# rftoy31.net
KiCad netlist of a schematic drawn in EAGLE
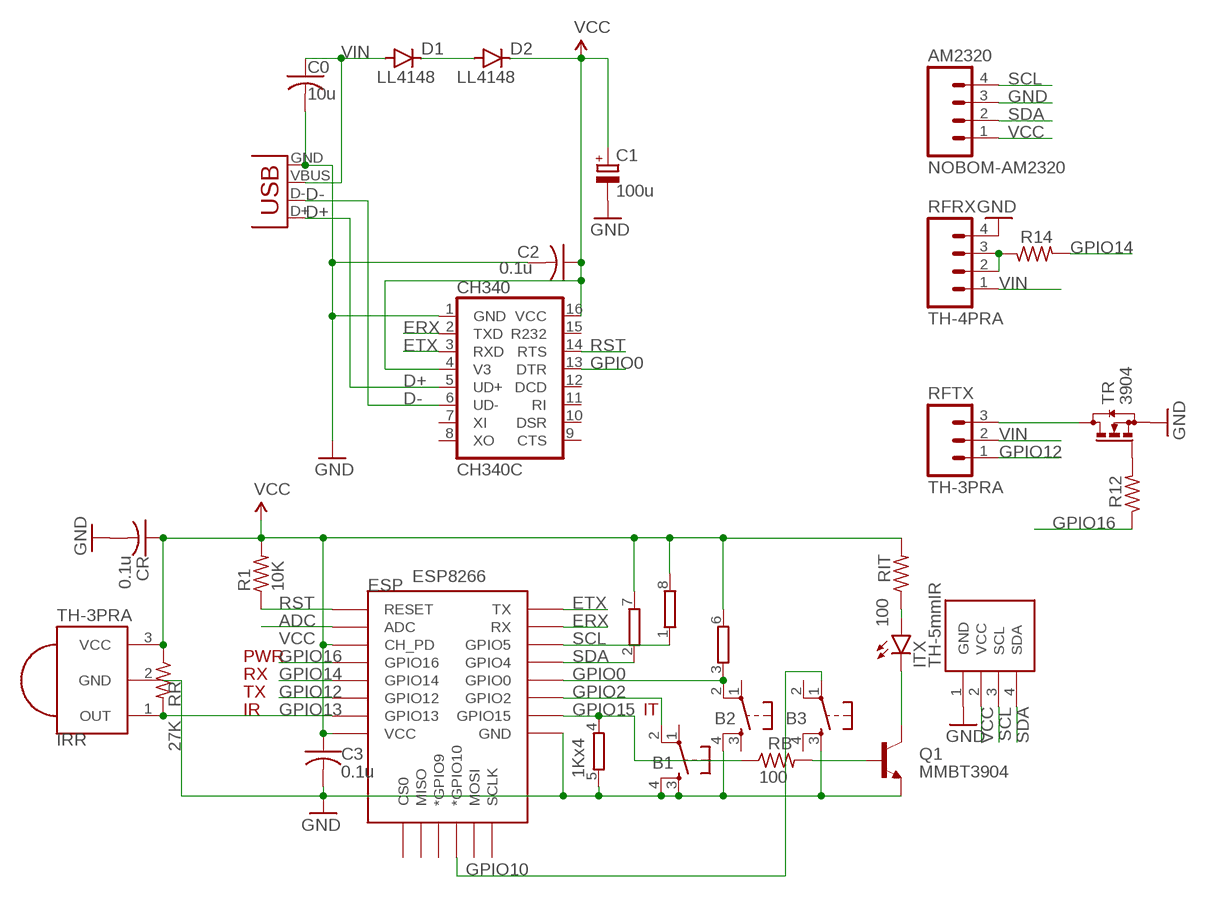
[diagram p0: schematic, sheet 1]

(export (version "E")
  (design (tool "Eeschema 10.0.6"))
  (components
    (comp (ref "AM2320")
      (value "NOBOM-AM2320")
      (footprint "eagle-import:1X04_NO_SILK")
      (libsource (lib "eagle-import") (part "M041X04_NO_SILK"))
    )
    (comp (ref "B1")
      (value "TH-TACT6x9")
      (footprint "eagle-import:EVQ-Q2-SMD")
      (libsource (lib "eagle-import") (part "SPST_TACT"))
    )
    (comp (ref "B2")
      (value "TH-TACT6x9")
      (footprint "eagle-import:EVQ-Q2-SMD")
      (libsource (lib "eagle-import") (part "SPST_TACT"))
    )
    (comp (ref "B3")
      (value "TH-TACT6x9")
      (footprint "eagle-import:EVQ-Q2-SMD")
      (libsource (lib "eagle-import") (part "SPST_TACT"))
    )
    (comp (ref "C0")
      (value "10u")
      (footprint "eagle-import:C0805K")
      (libsource (lib "eagle-import") (part "adafruit2013_C-USC0805K"))
    )
    (comp (ref "C1")
      (value "100u")
      (footprint "eagle-import:PANASONIC_C")
      (libsource (lib "eagle-import") (part "CPOL-EUC"))
    )
    (comp (ref "C2")
      (value "0.1u")
      (footprint "eagle-import:C0603K")
      (libsource (lib "eagle-import") (part "C-USC0603K"))
    )
    (comp (ref "C3")
      (value "0.1u")
      (footprint "eagle-import:C0603")
      (libsource (lib "eagle-import") (part "C-USC0603"))
    )
    (comp (ref "CH340")
      (value "CH340C")
      (footprint "eagle-import:SO16")
      (libsource (lib "eagle-import") (part "CH340G"))
    )
    (comp (ref "CR")
      (value "0.1u")
      (footprint "eagle-import:C0603")
      (libsource (lib "eagle-import") (part "C-USC0603"))
    )
    (comp (ref "D1")
      (value "LL4148")
      (footprint "eagle-import:MINIMELF")
      (libsource (lib "eagle-import") (part "DIODE-MINIMELF"))
    )
    (comp (ref "D2")
      (value "LL4148")
      (footprint "eagle-import:MINIMELF")
      (libsource (lib "eagle-import") (part "DIODE-MINIMELF"))
    )
    (comp (ref "ESP")
      (value "ESP8266")
      (footprint "eagle-import:ESP12E-SMD")
      (libsource (lib "eagle-import") (part "ESP12ESMD"))
    )
    (comp (ref "IRR")
      (value "TH-3PRA")
      (footprint "eagle-import:PNA460XM")
      (libsource (lib "eagle-import") (part "PNA460XM"))
    )
    (comp (ref "ITX")
      (value "TH-5mmIR")
      (footprint "eagle-import:IRL80A")
      (libsource (lib "eagle-import") (part "LEDIRL80A"))
    )
    (comp (ref "LCD")
      (value "NOBOM-OLED")
      (footprint "eagle-import:SSD1306_OLED_I2C_PCB_0.75_B")
      (libsource (lib "eagle-import") (part "SSD1306_OLED_I2CPCB0.75B"))
    )
    (comp (ref "Q1")
      (value "MMBT3904")
      (footprint "eagle-import:SOT23")
      (libsource (lib "eagle-import") (part "TRANSISTOR_NPNSOT23"))
    )
    (comp (ref "R1")
      (value "10K")
      (footprint "eagle-import:R0603")
      (libsource (lib "eagle-import") (part "R-US_R0603"))
    )
    (comp (ref "R12")
      (value "1K")
      (footprint "eagle-import:R0603")
      (libsource (lib "eagle-import") (part "adafruitGood_R-US_R0603"))
    )
    (comp (ref "R14")
      (value "1K")
      (footprint "eagle-import:R0603")
      (libsource (lib "eagle-import") (part "adafruitGood_R-US_R0603"))
    )
    (comp (ref "RB")
      (value "100")
      (footprint "eagle-import:R0603")
      (libsource (lib "eagle-import") (part "R-US_R0603"))
    )
    (comp (ref "RFRX")
      (value "TH-4PRA")
      (footprint "eagle-import:1X04_LONGPADS")
      (libsource (lib "eagle-import") (part "M04LONGPADS"))
    )
    (comp (ref "RFTX")
      (value "TH-3PRA")
      (footprint "eagle-import:1X03_NO_SILK")
      (libsource (lib "eagle-import") (part "M031X03_NO_SILK"))
    )
    (comp (ref "RIT")
      (value "100")
      (footprint "eagle-import:R0603")
      (libsource (lib "eagle-import") (part "R-US_R0603"))
    )
    (comp (ref "RN1")
      (value "1Kx4")
      (footprint "eagle-import:EXB38V")
      (libsource (lib "eagle-import") (part "4R-NEXB38V"))
    )
    (comp (ref "RR")
      (value "27K")
      (footprint "eagle-import:R0603")
      (libsource (lib "eagle-import") (part "R-US_R0603"))
    )
    (comp (ref "TR")
      (value "3904")
      (footprint "eagle-import:SOT23")
      (libsource (lib "eagle-import") (part "BSS123"))
    )
    (comp (ref "X3")
      (value "USBMICROB2")
      (footprint "eagle-import:USB-MICROB2")
      (libsource (lib "eagle-import") (part "USBMICROB2"))
    )
  )
  (nets
    (net (code "1") (name "/ADC") (class "Default")
      (node (ref "ESP") (pin "ADC") (pinfunction "ADC_ADC") (pintype "bidirectional"))
    )
    (net (code "2") (name "/D+") (class "Default")
      (node (ref "CH340") (pin "5") (pinfunction "UD+_5") (pintype "bidirectional"))
      (node (ref "X3") (pin "D+") (pinfunction "D+_D+") (pintype "bidirectional"))
    )
    (net (code "3") (name "/D-") (class "Default")
      (node (ref "CH340") (pin "6") (pinfunction "UD-_6") (pintype "bidirectional"))
      (node (ref "X3") (pin "D-") (pinfunction "D-_D-") (pintype "bidirectional"))
    )
    (net (code "4") (name "/ERX") (class "Default")
      (node (ref "CH340") (pin "2") (pinfunction "TXD_2") (pintype "bidirectional"))
      (node (ref "ESP") (pin "RXD0") (pinfunction "RX_RXD0") (pintype "bidirectional"))
    )
    (net (code "5") (name "/ETX") (class "Default")
      (node (ref "CH340") (pin "3") (pinfunction "RXD_3") (pintype "bidirectional"))
      (node (ref "ESP") (pin "TXD0") (pinfunction "TX_TXD0") (pintype "bidirectional"))
    )
    (net (code "6") (name "/GPIO0") (class "Default")
      (node (ref "B2") (pin "2") (pinfunction "2_2") (pintype "passive"))
      (node (ref "CH340") (pin "13") (pinfunction "DTR_13") (pintype "bidirectional"))
      (node (ref "ESP") (pin "GPIO0") (pinfunction "GPIO0_GPIO0") (pintype "bidirectional"))
      (node (ref "RN1") (pin "3") (pinfunction "1_3") (pintype "passive"))
    )
    (net (code "7") (name "/GPIO2") (class "Default")
      (node (ref "B1") (pin "2") (pinfunction "2_2") (pintype "passive"))
      (node (ref "ESP") (pin "GPIO2") (pinfunction "GPIO2_GPIO2") (pintype "bidirectional"))
    )
    (net (code "8") (name "/GPIO10") (class "Default")
      (node (ref "B3") (pin "1") (pinfunction "1_1") (pintype "passive"))
      (node (ref "ESP") (pin "GPIO10") (pinfunction "*GPIO10_GPIO10") (pintype "bidirectional"))
    )
    (net (code "9") (name "/GPIO12") (class "Default")
      (node (ref "ESP") (pin "GPIO12") (pinfunction "GPIO12_GPIO12") (pintype "bidirectional"))
      (node (ref "RFTX") (pin "1") (pinfunction "1_1") (pintype "passive"))
    )
    (net (code "10") (name "/GPIO13") (class "Default")
      (node (ref "ESP") (pin "GPIO13") (pinfunction "GPIO13_GPIO13") (pintype "bidirectional"))
      (node (ref "IRR") (pin "1") (pinfunction "OUT_1") (pintype "output"))
      (node (ref "RR") (pin "2") (pinfunction "2_2") (pintype "passive"))
    )
    (net (code "11") (name "/GPIO14") (class "Default")
      (node (ref "ESP") (pin "GPIO14") (pinfunction "GPIO14_GPIO14") (pintype "bidirectional"))
      (node (ref "R14") (pin "2") (pinfunction "2_2") (pintype "passive"))
    )
    (net (code "12") (name "/GPIO15") (class "Default")
      (node (ref "ESP") (pin "GPIO15") (pinfunction "GPIO15_GPIO15") (pintype "bidirectional"))
      (node (ref "RB") (pin "1") (pinfunction "1_1") (pintype "passive"))
      (node (ref "RN1") (pin "4") (pinfunction "1_4") (pintype "passive"))
    )
    (net (code "13") (name "/GPIO16") (class "Default")
      (node (ref "ESP") (pin "GPIO16") (pinfunction "GPIO16_GPIO16") (pintype "bidirectional"))
      (node (ref "R12") (pin "1") (pinfunction "1_1") (pintype "passive"))
    )
    (net (code "14") (name "/RST") (class "Default")
      (node (ref "CH340") (pin "14") (pinfunction "RTS_14") (pintype "bidirectional"))
      (node (ref "ESP") (pin "RESET") (pinfunction "RESET_RESET") (pintype "bidirectional"))
      (node (ref "R1") (pin "1") (pinfunction "1_1") (pintype "passive"))
    )
    (net (code "15") (name "/SCL") (class "Default")
      (node (ref "AM2320") (pin "4") (pinfunction "4_4") (pintype "passive"))
      (node (ref "ESP") (pin "GPIO5") (pinfunction "GPIO5_GPIO5") (pintype "bidirectional"))
      (node (ref "LCD") (pin "3") (pinfunction "SCL_3") (pintype "bidirectional"))
      (node (ref "RN1") (pin "1") (pinfunction "1_1") (pintype "passive"))
    )
    (net (code "16") (name "/SDA") (class "Default")
      (node (ref "AM2320") (pin "2") (pinfunction "2_2") (pintype "passive"))
      (node (ref "ESP") (pin "GPIO4") (pinfunction "GPIO4_GPIO4") (pintype "bidirectional"))
      (node (ref "LCD") (pin "4") (pinfunction "SDA_4") (pintype "bidirectional"))
      (node (ref "RN1") (pin "2") (pinfunction "1_2") (pintype "passive"))
    )
    (net (code "17") (name "/VIN") (class "Default")
      (node (ref "C0") (pin "1") (pinfunction "1_1") (pintype "passive"))
      (node (ref "D1") (pin "A") (pinfunction "A_A") (pintype "passive"))
      (node (ref "RFRX") (pin "1") (pinfunction "1_1") (pintype "passive"))
      (node (ref "RFTX") (pin "2") (pinfunction "2_2") (pintype "passive"))
      (node (ref "X3") (pin "VBUS") (pinfunction "VBUS_VBUS") (pintype "bidirectional"))
    )
    (net (code "18") (name "GND") (class "Default")
      (node (ref "AM2320") (pin "3") (pinfunction "3_3") (pintype "passive"))
      (node (ref "B1") (pin "3") (pinfunction "3_3") (pintype "passive"))
      (node (ref "B1") (pin "4") (pinfunction "4_4") (pintype "passive"))
      (node (ref "B2") (pin "4") (pinfunction "4_4") (pintype "passive"))
      (node (ref "B3") (pin "3") (pinfunction "3_3") (pintype "passive"))
      (node (ref "C0") (pin "2") (pinfunction "2_2") (pintype "passive"))
      (node (ref "C1") (pin "-") (pinfunction "-_-") (pintype "passive"))
      (node (ref "C2") (pin "2") (pinfunction "2_2") (pintype "passive"))
      (node (ref "C3") (pin "2") (pinfunction "2_2") (pintype "passive"))
      (node (ref "CH340") (pin "1") (pinfunction "GND_1") (pintype "power_in"))
      (node (ref "CR") (pin "2") (pinfunction "2_2") (pintype "passive"))
      (node (ref "ESP") (pin "GND") (pinfunction "GND_GND") (pintype "bidirectional"))
      (node (ref "IRR") (pin "2") (pinfunction "GND_2") (pintype "power_in"))
      (node (ref "LCD") (pin "1") (pinfunction "GND_1") (pintype "power_in"))
      (node (ref "Q1") (pin "2") (pinfunction "E_2") (pintype "passive"))
      (node (ref "RFRX") (pin "4") (pinfunction "4_4") (pintype "passive"))
      (node (ref "RN1") (pin "5") (pinfunction "2_5") (pintype "passive"))
      (node (ref "TR") (pin "2") (pinfunction "S_2") (pintype "passive"))
      (node (ref "X3") (pin "GND") (pinfunction "GND_GND") (pintype "bidirectional"))
    )
    (net (code "19") (name "Net-(D1-PadC)") (class "Default")
      (node (ref "D1") (pin "C") (pinfunction "C_C") (pintype "passive"))
      (node (ref "D2") (pin "A") (pinfunction "A_A") (pintype "passive"))
    )
    (net (code "20") (name "Net-(ITX-C)") (class "Default")
      (node (ref "ITX") (pin "K") (pinfunction "C_K") (pintype "passive"))
      (node (ref "Q1") (pin "3") (pinfunction "C_3") (pintype "passive"))
    )
    (net (code "21") (name "Net-(ITX-PadA)") (class "Default")
      (node (ref "ITX") (pin "A") (pinfunction "A_A") (pintype "passive"))
      (node (ref "RIT") (pin "1") (pinfunction "1_1") (pintype "passive"))
    )
    (net (code "22") (name "Net-(Q1-B)") (class "Default")
      (node (ref "Q1") (pin "1") (pinfunction "B_1") (pintype "passive"))
      (node (ref "RB") (pin "2") (pinfunction "2_2") (pintype "passive"))
    )
    (net (code "23") (name "Net-(R14-Pad1)") (class "Default")
      (node (ref "R14") (pin "1") (pinfunction "1_1") (pintype "passive"))
      (node (ref "RFRX") (pin "2") (pinfunction "2_2") (pintype "passive"))
      (node (ref "RFRX") (pin "3") (pinfunction "3_3") (pintype "passive"))
    )
    (net (code "24") (name "Net-(TR-D)") (class "Default")
      (node (ref "RFTX") (pin "3") (pinfunction "3_3") (pintype "passive"))
      (node (ref "TR") (pin "3") (pinfunction "D_3") (pintype "passive"))
    )
    (net (code "25") (name "Net-(TR-G)") (class "Default")
      (node (ref "R12") (pin "2") (pinfunction "2_2") (pintype "passive"))
      (node (ref "TR") (pin "1") (pinfunction "G_1") (pintype "passive"))
    )
    (net (code "26") (name "VCC") (class "Default")
      (node (ref "AM2320") (pin "1") (pinfunction "1_1") (pintype "passive"))
      (node (ref "C1") (pin "+") (pinfunction "+_+") (pintype "passive"))
      (node (ref "C2") (pin "1") (pinfunction "1_1") (pintype "passive"))
      (node (ref "C3") (pin "1") (pinfunction "1_1") (pintype "passive"))
      (node (ref "CH340") (pin "16") (pinfunction "VCC_16") (pintype "power_in"))
      (node (ref "CH340") (pin "4") (pinfunction "V3_4") (pintype "bidirectional"))
      (node (ref "CR") (pin "1") (pinfunction "1_1") (pintype "passive"))
      (node (ref "D2") (pin "C") (pinfunction "C_C") (pintype "passive"))
      (node (ref "ESP") (pin "CH_PD") (pinfunction "CH_PD_CH_PD") (pintype "bidirectional"))
      (node (ref "ESP") (pin "VCC") (pinfunction "VCC_VCC") (pintype "bidirectional"))
      (node (ref "IRR") (pin "3") (pinfunction "VCC_3") (pintype "power_in"))
      (node (ref "LCD") (pin "2") (pinfunction "VCC_2") (pintype "power_in"))
      (node (ref "R1") (pin "2") (pinfunction "2_2") (pintype "passive"))
      (node (ref "RIT") (pin "2") (pinfunction "2_2") (pintype "passive"))
      (node (ref "RN1") (pin "6") (pinfunction "2_6") (pintype "passive"))
      (node (ref "RN1") (pin "7") (pinfunction "2_7") (pintype "passive"))
      (node (ref "RN1") (pin "8") (pinfunction "2_8") (pintype "passive"))
      (node (ref "RR") (pin "1") (pinfunction "1_1") (pintype "passive"))
    )
    (net (code "27") (name "unconnected-(B1-Pad1)") (class "Default")
      (node (ref "B1") (pin "1") (pinfunction "1_1") (pintype "passive"))
    )
    (net (code "28") (name "unconnected-(B2-Pad1)") (class "Default")
      (node (ref "B2") (pin "1") (pinfunction "1_1") (pintype "passive"))
    )
    (net (code "29") (name "unconnected-(B2-Pad3)") (class "Default")
      (node (ref "B2") (pin "3") (pinfunction "3_3") (pintype "passive"))
    )
    (net (code "30") (name "unconnected-(B3-Pad2)") (class "Default")
      (node (ref "B3") (pin "2") (pinfunction "2_2") (pintype "passive"))
    )
    (net (code "31") (name "unconnected-(B3-Pad4)") (class "Default")
      (node (ref "B3") (pin "4") (pinfunction "4_4") (pintype "passive"))
    )
    (net (code "32") (name "unconnected-(CH340-CTS-Pad9)") (class "Default")
      (node (ref "CH340") (pin "9") (pinfunction "CTS_9") (pintype "bidirectional"))
    )
    (net (code "33") (name "unconnected-(CH340-DCD-Pad12)") (class "Default")
      (node (ref "CH340") (pin "12") (pinfunction "DCD_12") (pintype "bidirectional"))
    )
    (net (code "34") (name "unconnected-(CH340-DSR-Pad10)") (class "Default")
      (node (ref "CH340") (pin "10") (pinfunction "DSR_10") (pintype "bidirectional"))
    )
    (net (code "35") (name "unconnected-(CH340-R232-Pad15)") (class "Default")
      (node (ref "CH340") (pin "15") (pinfunction "R232_15") (pintype "bidirectional"))
    )
    (net (code "36") (name "unconnected-(CH340-RI-Pad11)") (class "Default")
      (node (ref "CH340") (pin "11") (pinfunction "RI_11") (pintype "bidirectional"))
    )
    (net (code "37") (name "unconnected-(CH340-XI-Pad7)") (class "Default")
      (node (ref "CH340") (pin "7") (pinfunction "XI_7") (pintype "bidirectional"))
    )
    (net (code "38") (name "unconnected-(CH340-XO-Pad8)") (class "Default")
      (node (ref "CH340") (pin "8") (pinfunction "XO_8") (pintype "bidirectional"))
    )
    (net (code "39") (name "unconnected-(ESP-*GPIO9-PadGPIO9)") (class "Default")
      (node (ref "ESP") (pin "GPIO9") (pinfunction "*GPIO9_GPIO9") (pintype "bidirectional"))
    )
    (net (code "40") (name "unconnected-(ESP-PadCS0)") (class "Default")
      (node (ref "ESP") (pin "CS0") (pinfunction "CS0_CS0") (pintype "bidirectional"))
    )
    (net (code "41") (name "unconnected-(ESP-PadMISO)") (class "Default")
      (node (ref "ESP") (pin "MISO") (pinfunction "MISO_MISO") (pintype "bidirectional"))
    )
    (net (code "42") (name "unconnected-(ESP-PadMOSI)") (class "Default")
      (node (ref "ESP") (pin "MOSI") (pinfunction "MOSI_MOSI") (pintype "bidirectional"))
    )
    (net (code "43") (name "unconnected-(ESP-PadSCLK)") (class "Default")
      (node (ref "ESP") (pin "SCLK") (pinfunction "SCLK_SCLK") (pintype "bidirectional"))
    )
  )
)
